# power_design_block.net
KiCad netlist of a schematic drawn in EAGLE
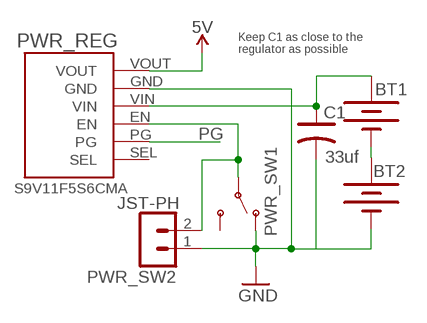
[diagram p0: schematic, sheet 1]

(export (version "E")
  (design (tool "Eeschema 10.0.6"))
  (components
    (comp (ref "BT1")
      (value "BATTERY-18650")
      (footprint "eagle-import:BATTERY_18650-HOLDER")
      (libsource (lib "eagle-import") (part "BATTERY-18650"))
    )
    (comp (ref "BT2")
      (value "BATTERY-18650")
      (footprint "eagle-import:BATTERY_18650-HOLDER")
      (libsource (lib "eagle-import") (part "BATTERY-18650"))
    )
    (comp (ref "C1")
      (value "33uf")
      (footprint "eagle-import:PC-D5.3MM")
      (fields (field (name "MPN") "KS 100uF/16V"))
      (libsource (lib "eagle-import") (part "DIP-ALUMINUM-47UF-16V(D5-H7MM)"))
    )
    (comp (ref "PWR_REG")
      (value "S9V11F5S6CMA")
      (footprint "eagle-import:S9V11F3S5CMA_BETTER_PINS")
      (libsource (lib "eagle-import") (part "S9V11F5S6CMANOSILKSCREENCRAP"))
    )
    (comp (ref "PWR_SW1")
      (value "SWITCH-SPDT-PTH-11.6X4.0MM-LOCK")
      (footprint "eagle-import:SWITCH_SPDT_PTH_11.6X4.0MM_LOCK")
      (libsource (lib "eagle-import") (part "SWITCH-SPDT-PTH-11.6X4.0MM-LOCK"))
    )
    (comp (ref "PWR_SW2")
      (value "JST-PH")
      (footprint "eagle-import:B2B-PH-K")
      (libsource (lib "eagle-import") (part "B2B-PH-K"))
    )
  )
  (nets
    (net (code "1") (name "/PG") (class "Default")
      (node (ref "PWR_REG") (pin "PG") (pinfunction "PG_PG") (pintype "bidirectional"))
    )
    (net (code "2") (name "5V") (class "Default")
      (node (ref "PWR_REG") (pin "VOUT") (pinfunction "VOUT_VOUT") (pintype "bidirectional"))
    )
    (net (code "3") (name "GND") (class "Default")
      (node (ref "BT2") (pin "GND@1") (pinfunction "-_GND@1") (pintype "power_in"))
      (node (ref "C1") (pin "-") (pinfunction "-_-") (pintype "passive"))
      (node (ref "PWR_REG") (pin "GND") (pinfunction "GND_GND") (pintype "bidirectional"))
      (node (ref "PWR_SW1") (pin "1") (pinfunction "O_1") (pintype "passive"))
      (node (ref "PWR_SW2") (pin "1") (pinfunction "1_1") (pintype "passive"))
    )
    (net (code "4") (name "Net-(BT1-+)") (class "Default")
      (node (ref "BT1") (pin "PWR@1") (pinfunction "+_PWR@1") (pintype "power_in"))
      (node (ref "C1") (pin "+") (pinfunction "+_+") (pintype "passive"))
      (node (ref "PWR_REG") (pin "VIN") (pinfunction "VIN_VIN") (pintype "bidirectional"))
    )
    (net (code "5") (name "Net-(BT1--)") (class "Default")
      (node (ref "BT1") (pin "GND@1") (pinfunction "-_GND@1") (pintype "power_in"))
      (node (ref "BT2") (pin "PWR@1") (pinfunction "+_PWR@1") (pintype "power_in"))
    )
    (net (code "6") (name "Net-(PWR_SW1-P)") (class "Default")
      (node (ref "PWR_REG") (pin "EN") (pinfunction "EN_EN") (pintype "bidirectional"))
      (node (ref "PWR_SW1") (pin "2") (pinfunction "P_2") (pintype "passive"))
      (node (ref "PWR_SW2") (pin "2") (pinfunction "2_2") (pintype "passive"))
    )
    (net (code "7") (name "unconnected-(PWR_REG-PadSEL)") (class "Default")
      (node (ref "PWR_REG") (pin "SEL") (pinfunction "SEL_SEL") (pintype "bidirectional"))
    )
    (net (code "8") (name "unconnected-(PWR_SW1-S-Pad3)") (class "Default")
      (node (ref "PWR_SW1") (pin "3") (pinfunction "S_3") (pintype "passive"))
    )
  )
)
